# Regulator3V3.net
KiCad netlist of a schematic drawn in Altium Designer
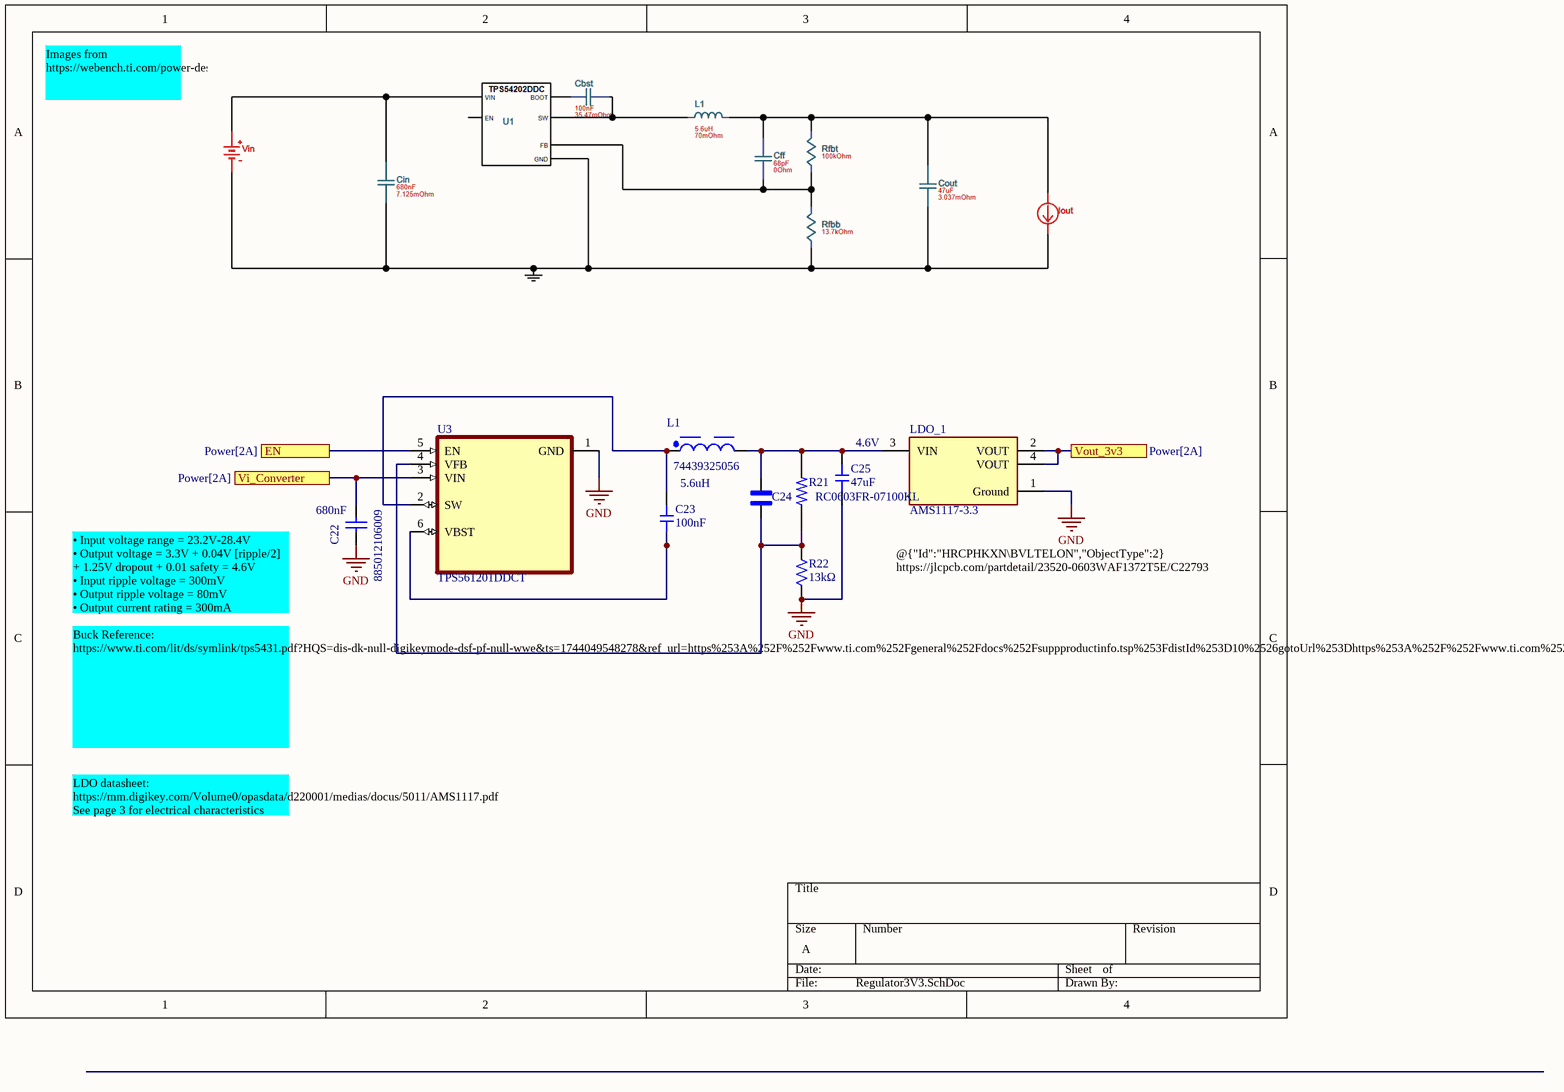
[diagram p0: Regulator3V3.SchDoc]

(export (version "E")
  (design (tool "Eeschema 10.0.6"))
  (components
    (comp (ref "C22")
      (value "885012106009")
      (footprint "WCAP-CSGP_0603_L1.6W0.8H0.8_Reflow")
      (description "Cap Cer 0.68UF 10V X5R 0603")
      (fields (field (name "TOLERANCE") "20%") (field (name "CAPACITANCE") "680nF"))
      (libsource (lib "Altium Content Vault") (part "Capacitor_Non-Polarized"))
    )
    (comp (ref "C23")
      (value "CL05B104KO5NNNC")
      (footprint "CAP-0402")
      (description "Capacitor, Ceramic (MLCC), 100nF, ±10%, 16V, X7R, ±10%, SMD 0402")
      (fields
        (field (name "JLCPCB BASIC PART") "Yes")
        (field (name "CAPACITANCE") "100nF")
        (field (name "JLCPCB PART NUMBER") "C1525")
      )
      (libsource (lib "jlcpcb_2024_10_capacitors_basic") (part "CL05B104KO5NNNC"))
    )
    (comp (ref "C24")
      (value "CGA1A2C0G1E680J030BA")
      (footprint "CAPC0603X33N")
      (description "68 pF Â±5% 25V Ceramic Capacitor C0G, NP0 0201 (0603 Metric)")
      (fields (field (name "MF") "TDK"))
      (libsource (lib "CGA1A2C0G1E680J030BA") (part "CGA1A2C0G1E680J030BA"))
    )
    (comp (ref "C25")
      (value "CL21A476MQYNNNE")
      (footprint "CAP-0805")
      (description "Capacitor, Ceramic (MLCC), 47uF, ±20%, 6.3V, X5R, ±20%, SMD 0805")
      (fields
        (field (name "JLCPCB BASIC PART") "Yes")
        (field (name "CAPACITANCE") "47uF")
        (field (name "JLCPCB PART NUMBER") "C16780")
      )
      (libsource (lib "jlcpcb_2024_10_capacitors_basic") (part "CL21A476MQYNNNE"))
    )
    (comp (ref "L1")
      (value "74439325056")
      (footprint "WE-XHMI_4040")
      (description "Power Inductor, 5.6UH, Shielded, 5.1A Rohs Compliant: Yes")
      (fields (field (name "PARAMETER 1") "5.6uH"))
      (libsource (lib "Altium Content Vault") (part "Inductor - 2"))
    )
    (comp (ref "LDO_1")
      (value "AMS1117-3.3")
      (footprint "FP-AMS1117-IPC_C")
      (description "LDO Voltage Regulators 1A, 3.3V")
      (fields
        (field (name "OCTOPART") "https://octopart.com/ams1117-3.3-advanced+monolithic+systems-25899300")
        (field (name "MANUFACTURER") "Advanced Monolithic Systems")
      )
      (libsource (lib "Altium Content Vault") (part "8bdbb5f8e77002000e30dd2845d0354"))
    )
    (comp (ref "R21")
      (value "RC0603FR-07100KL")
      (footprint "RESC1607X60N")
      (description "100 kOhms Â±1% 0.1W, 1/10W Chip Resistor 0603 (1608 Metric) Moisture Resistant Thick Film")
      (fields (field (name "MF") "Yageo"))
      (libsource (lib "RC0603FR-07100KL") (part "RC0603FR-07100KL"))
    )
    (comp (ref "R22")
      (value "0603WAF1302T5E")
      (footprint "RES-0603")
      (description "Resistor, 13kΩ, ±1%, 100mW, 75V, ±100ppm/℃, -55℃~+155℃, SMD 0603")
      (fields
        (field (name "MANUFACTURER") "Uniroyal")
        (field (name "JLCPCB PART NUMBER") "C22797")
        (field (name "RESISTANCE") "13kΩ")
      )
      (libsource (lib "jlcpcb_2024_10_resistors_basic") (part "0603WAF1302T5E"))
    )
    (comp (ref "U3")
      (value "TPS561201DDCT")
      (footprint "SOT95P280X110-6N")
      (description "4.5V to 17V Input, 1A Synchronous Step-Down Voltage Regulator in 6-pin SOT-23")
      (fields (field (name "MF") "Texas Instruments"))
      (libsource (lib "TPS561201DDCT") (part "TPS561201DDCT"))
    )
  )
  (nets
    (net (code "1") (name "/EN") (class "Default")
      (node (ref "U3") (pin "5") (pinfunction "EN_5") (pintype "input"))
    )
    (net (code "2") (name "/Vi_Converter") (class "Default")
      (node (ref "C22") (pin "2") (pinfunction "2_2") (pintype "passive"))
      (node (ref "U3") (pin "3") (pinfunction "VIN_3") (pintype "input"))
    )
    (net (code "3") (name "/Vout_3v3") (class "Default")
      (node (ref "LDO_1") (pin "2") (pinfunction "VOUT_2") (pintype "passive"))
      (node (ref "LDO_1") (pin "4") (pinfunction "VOUT_4") (pintype "passive"))
    )
    (net (code "4") (name "GND") (class "Default")
      (node (ref "C22") (pin "1") (pinfunction "1_1") (pintype "passive"))
      (node (ref "C25") (pin "1") (pinfunction "1_1") (pintype "passive"))
      (node (ref "LDO_1") (pin "1") (pinfunction "Ground_1") (pintype "power_in"))
      (node (ref "R22") (pin "1") (pinfunction "1_1") (pintype "passive"))
      (node (ref "U3") (pin "1") (pinfunction "GND_1") (pintype "power_in"))
    )
    (net (code "5") (name "Net-(LDO_1-VIN)") (class "Default")
      (node (ref "C24") (pin "2") (pinfunction "2_2") (pintype "passive"))
      (node (ref "C25") (pin "2") (pinfunction "2_2") (pintype "passive"))
      (node (ref "L1") (pin "2") (pinfunction "2_2") (pintype "passive"))
      (node (ref "LDO_1") (pin "3") (pinfunction "VIN_3") (pintype "power_in"))
      (node (ref "R21") (pin "2") (pinfunction "2_2") (pintype "passive"))
    )
    (net (code "6") (name "Net-(U3-SW)") (class "Default")
      (node (ref "C23") (pin "2") (pinfunction "2_2") (pintype "passive"))
      (node (ref "L1") (pin "1") (pinfunction "1_1") (pintype "passive"))
      (node (ref "U3") (pin "2") (pinfunction "SW_2") (pintype "bidirectional"))
    )
    (net (code "7") (name "Net-(U3-VBST)") (class "Default")
      (node (ref "C23") (pin "1") (pinfunction "1_1") (pintype "passive"))
      (node (ref "U3") (pin "6") (pinfunction "VBST_6") (pintype "bidirectional"))
    )
    (net (code "8") (name "Net-(U3-VFB)") (class "Default")
      (node (ref "C24") (pin "1") (pinfunction "1_1") (pintype "passive"))
      (node (ref "R21") (pin "1") (pinfunction "1_1") (pintype "passive"))
      (node (ref "R22") (pin "2") (pinfunction "2_2") (pintype "passive"))
      (node (ref "U3") (pin "4") (pinfunction "VFB_4") (pintype "input"))
    )
  )
)
